# RadioNetwork.net
KiCad netlist of a schematic drawn in EAGLE
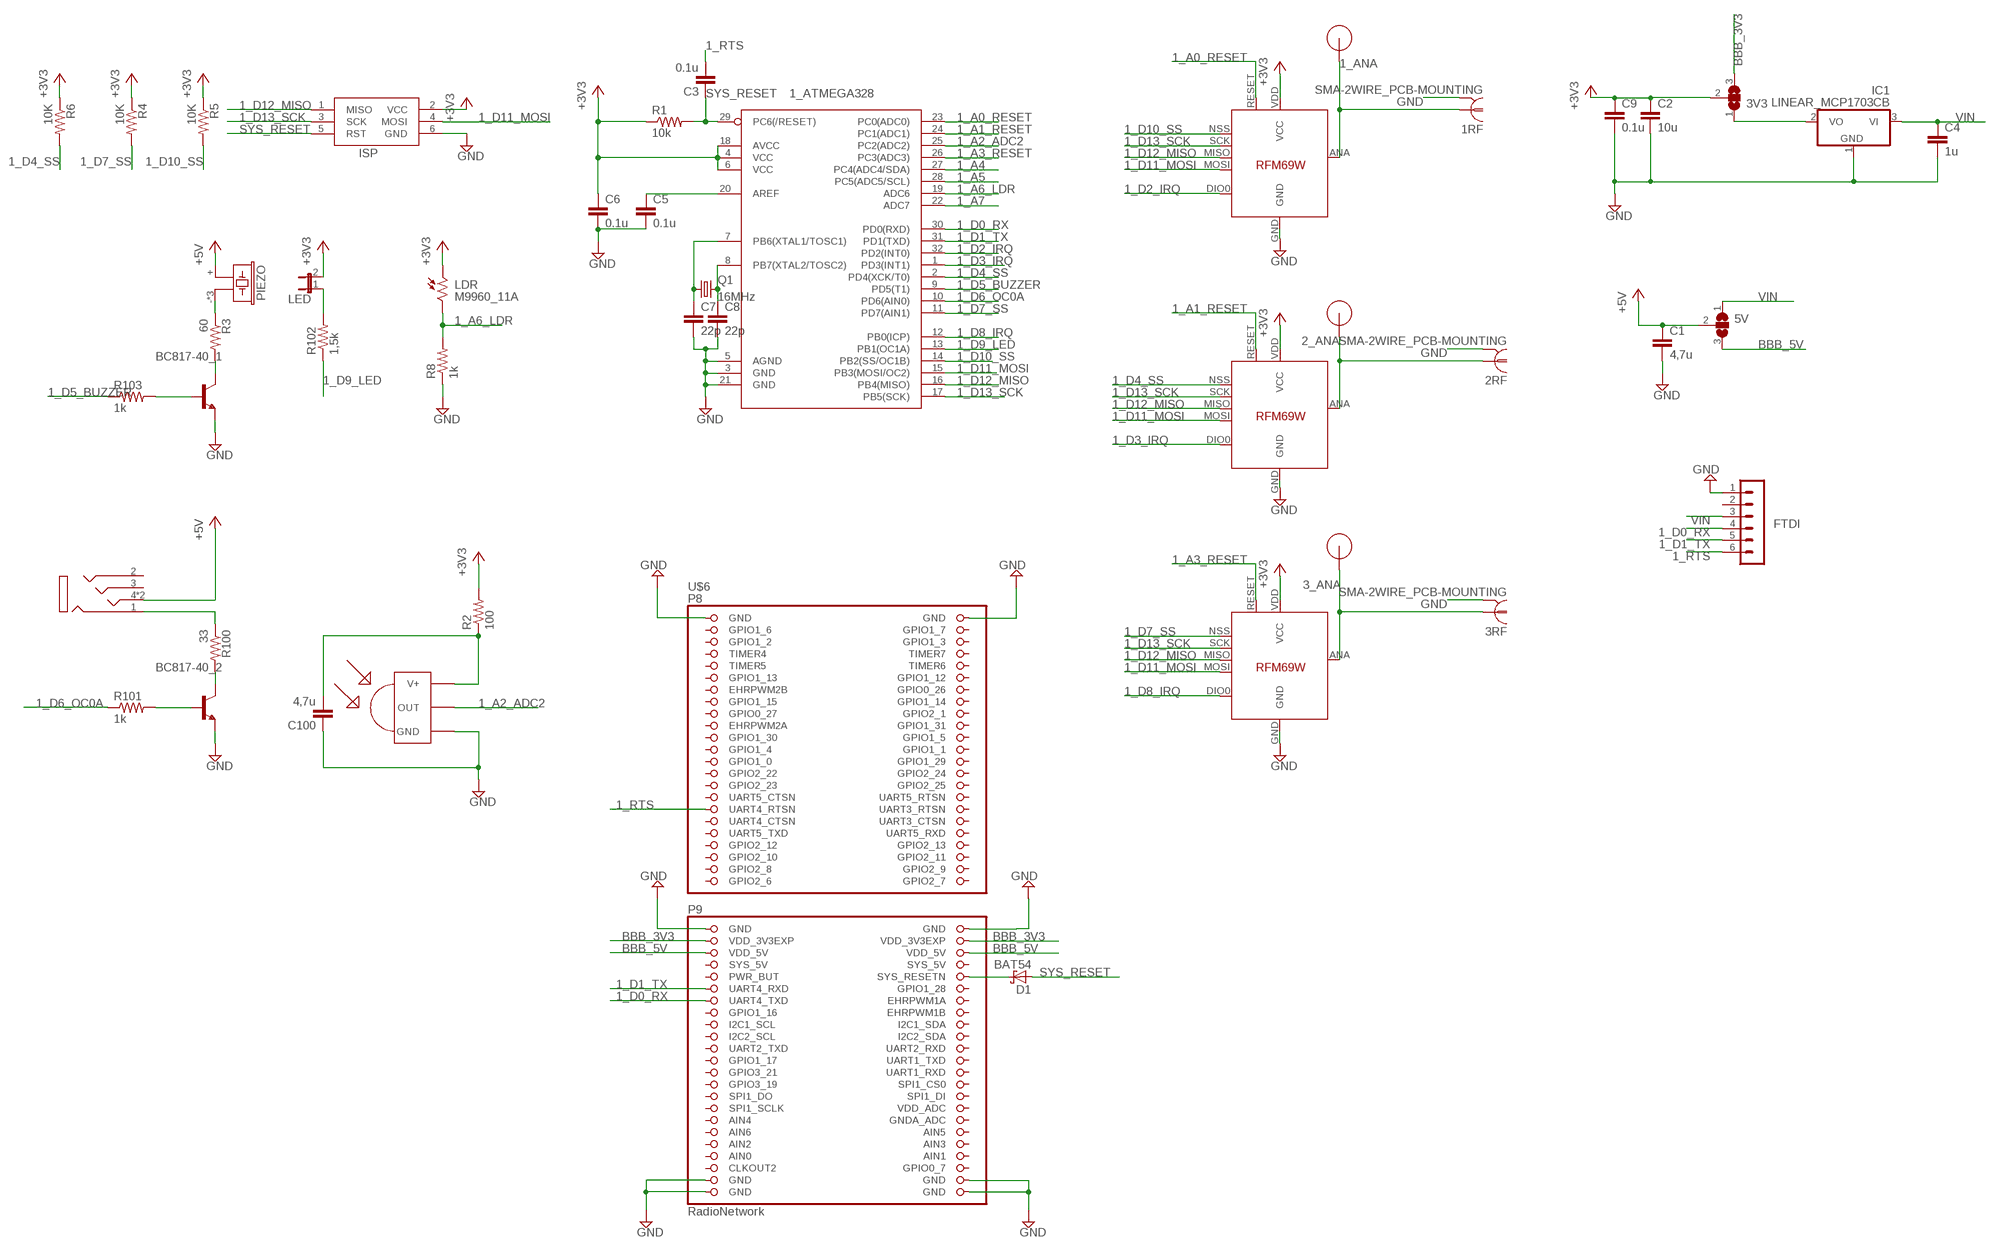
[diagram p0: schematic, sheet 1]

(export (version "E")
  (design (tool "Eeschema 10.0.6"))
  (components
    (comp (ref "1RF")
      (value "SMA-2WIRE_PCB-MOUNTING")
      (footprint "eagle-import:J01151A0931")
      (libsource (lib "eagle-import") (part "SMA-2WIRE_PCB-MOUNTING"))
    )
    (comp (ref "1_ATMEGA328")
      (value "ATMega-328")
      (footprint "eagle-import:TQFP32-08")
      (libsource (lib "eagle-import") (part "ATMEGA168/328TQFP32"))
    )
    (comp (ref "1_RFM69")
      (value "RFM69_MINIPADS")
      (footprint "eagle-import:RFM69W-MINPADS")
      (libsource (lib "eagle-import") (part "RFM69_MINIPADS"))
    )
    (comp (ref "2RF")
      (value "SMA-2WIRE_PCB-MOUNTING")
      (footprint "eagle-import:J01151A0931")
      (libsource (lib "eagle-import") (part "SMA-2WIRE_PCB-MOUNTING"))
    )
    (comp (ref "2_RFM69")
      (value "RFM69_MINIPADS")
      (footprint "eagle-import:RFM69W-MINPADS")
      (libsource (lib "eagle-import") (part "RFM69_MINIPADS"))
    )
    (comp (ref "3RF")
      (value "SMA-2WIRE_PCB-MOUNTING")
      (footprint "eagle-import:J01151A0931")
      (libsource (lib "eagle-import") (part "SMA-2WIRE_PCB-MOUNTING"))
    )
    (comp (ref "3V3")
      (value "SJ2W")
      (footprint "eagle-import:SJ_2")
      (libsource (lib "eagle-import") (part "SJ2W"))
    )
    (comp (ref "3_RFM69")
      (value "RFM69_MINIPADS")
      (footprint "eagle-import:RFM69W-MINPADS")
      (libsource (lib "eagle-import") (part "RFM69_MINIPADS"))
    )
    (comp (ref "5V")
      (value "SJ2W")
      (footprint "eagle-import:SJ_2")
      (libsource (lib "eagle-import") (part "SJ2W"))
    )
    (comp (ref "BC817-40_1")
      (value "BC817-40-NPN-SOT23-BEC")
      (footprint "eagle-import:SOT23-BEC")
      (libsource (lib "eagle-import") (part "-NPN-SOT23-BECBC817-40"))
    )
    (comp (ref "BC817-40_2")
      (value "BC817-40-NPN-SOT23-BEC")
      (footprint "eagle-import:SOT23-BEC")
      (libsource (lib "eagle-import") (part "-NPN-SOT23-BECBC817-40"))
    )
    (comp (ref "C1")
      (value "4,7u")
      (footprint "eagle-import:0603-CAP")
      (libsource (lib "eagle-import") (part "CAP0603-CAP"))
    )
    (comp (ref "C2")
      (value "10u")
      (footprint "eagle-import:0603-CAP")
      (libsource (lib "eagle-import") (part "CAP0603-CAP"))
    )
    (comp (ref "C3")
      (value "0.1u")
      (footprint "eagle-import:0603-CAP")
      (libsource (lib "eagle-import") (part "CAP0603-CAP"))
    )
    (comp (ref "C4")
      (value "1u")
      (footprint "eagle-import:0603-CAP")
      (libsource (lib "eagle-import") (part "CAP0603-CAP"))
    )
    (comp (ref "C5")
      (value "0.1u")
      (footprint "eagle-import:0603-CAP")
      (libsource (lib "eagle-import") (part "CAP0603-CAP"))
    )
    (comp (ref "C6")
      (value "0.1u")
      (footprint "eagle-import:0603-CAP")
      (libsource (lib "eagle-import") (part "CAP0603-CAP"))
    )
    (comp (ref "C7")
      (value "22p")
      (footprint "eagle-import:0603-CAP")
      (libsource (lib "eagle-import") (part "CAP0603-CAP"))
    )
    (comp (ref "C8")
      (value "22p")
      (footprint "eagle-import:0603-CAP")
      (libsource (lib "eagle-import") (part "CAP0603-CAP"))
    )
    (comp (ref "C9")
      (value "0.1u")
      (footprint "eagle-import:0603-CAP")
      (libsource (lib "eagle-import") (part "CAP0603-CAP"))
    )
    (comp (ref "C100")
      (value "4,7u")
      (footprint "eagle-import:0603-CAP")
      (libsource (lib "eagle-import") (part "CAP0603-CAP"))
    )
    (comp (ref "D1")
      (value "BAT54")
      (footprint "eagle-import:SOT23")
      (libsource (lib "eagle-import") (part "BAT54"))
    )
    (comp (ref "FTDI")
      (value "FTDI")
      (footprint "eagle-import:MA06-1")
      (libsource (lib "eagle-import") (part "MA06-1"))
    )
    (comp (ref "IC1")
      (value "LINEAR_MCP1703CB")
      (footprint "eagle-import:LINEAR_SOT23")
      (libsource (lib "eagle-import") (part "LINEAR_MCP1703CB"))
    )
    (comp (ref "IR-RX")
      (value "TSOP4836")
      (footprint "eagle-import:TSOP18XX")
      (libsource (lib "eagle-import") (part "TSOP4836"))
    )
    (comp (ref "IR-TX")
      (value "1503_13")
      (footprint "eagle-import:1503-03")
      (libsource (lib "eagle-import") (part "1503_13"))
    )
    (comp (ref "ISP")
      (value "AVRISP-6")
      (footprint "eagle-import:AVRISP")
      (libsource (lib "eagle-import") (part "AVRISP-6"))
    )
    (comp (ref "LDR")
      (value "M9960_11A")
      (footprint "eagle-import:M9960")
      (libsource (lib "eagle-import") (part "M9960_11A"))
    )
    (comp (ref "LED")
      (value "JP1E")
      (footprint "eagle-import:JP1")
      (libsource (lib "eagle-import") (part "JP1E"))
    )
    (comp (ref "PIEZO")
      (value "BUZZER-PIEZO_SMD")
      (footprint "eagle-import:BUZZER-PIEZO_SMD")
      (libsource (lib "eagle-import") (part "BUZZER-PIEZO_SMD"))
    )
    (comp (ref "Q1")
      (value "16MHz")
      (footprint "eagle-import:HC49_S")
      (libsource (lib "eagle-import") (part "CRYSTALHC49S"))
    )
    (comp (ref "R1")
      (value "10k")
      (footprint "eagle-import:0603-RES")
      (libsource (lib "eagle-import") (part "RESISTOR0603-RES"))
    )
    (comp (ref "R2")
      (value "100")
      (footprint "eagle-import:0603-RES")
      (libsource (lib "eagle-import") (part "RESISTOR0603-RES"))
    )
    (comp (ref "R3")
      (value "60")
      (footprint "eagle-import:0603-RES")
      (libsource (lib "eagle-import") (part "RESISTOR0603-RES"))
    )
    (comp (ref "R4")
      (value "10K")
      (footprint "eagle-import:0603-RES")
      (libsource (lib "eagle-import") (part "RESISTOR0603-RES"))
    )
    (comp (ref "R5")
      (value "10K")
      (footprint "eagle-import:0603-RES")
      (libsource (lib "eagle-import") (part "RESISTOR0603-RES"))
    )
    (comp (ref "R6")
      (value "10K")
      (footprint "eagle-import:0603-RES")
      (libsource (lib "eagle-import") (part "RESISTOR0603-RES"))
    )
    (comp (ref "R8")
      (value "1k")
      (footprint "eagle-import:0603-RES")
      (libsource (lib "eagle-import") (part "RESISTOR0603-RES"))
    )
    (comp (ref "R100")
      (value "33")
      (footprint "eagle-import:0603-RES")
      (libsource (lib "eagle-import") (part "RESISTOR0603-RES"))
    )
    (comp (ref "R101")
      (value "1k")
      (footprint "eagle-import:0603-RES")
      (libsource (lib "eagle-import") (part "RESISTOR0603-RES"))
    )
    (comp (ref "R102")
      (value "1,5k")
      (footprint "eagle-import:0603-RES")
      (libsource (lib "eagle-import") (part "RESISTOR0603-RES"))
    )
    (comp (ref "R103")
      (value "1k")
      (footprint "eagle-import:0603-RES")
      (libsource (lib "eagle-import") (part "RESISTOR0603-RES"))
    )
    (comp (ref "U$1")
      (value "RFM12B_ANTENNA")
      (footprint "eagle-import:RFM12B-ANTENNA")
      (libsource (lib "eagle-import") (part "RFM12B_ANTENNA"))
    )
    (comp (ref "U$2")
      (value "RFM12B_ANTENNA")
      (footprint "eagle-import:RFM12B-ANTENNA")
      (libsource (lib "eagle-import") (part "RFM12B_ANTENNA"))
    )
    (comp (ref "U$5")
      (value "RFM12B_ANTENNA")
      (footprint "eagle-import:RFM12B-ANTENNA")
      (libsource (lib "eagle-import") (part "RFM12B_ANTENNA"))
    )
    (comp (ref "U$6")
      (value "RadioNetwork")
      (footprint "eagle-import:BEAGLEBONE_SHIELD")
      (libsource (lib "eagle-import") (part "BEAGLEBONE_OUTLINE"))
    )
  )
  (nets
    (net (code "1") (name "+3V3") (class "Default")
      (node (ref "1_ATMEGA328") (pin "18") (pinfunction "AVCC_18") (pintype "bidirectional"))
      (node (ref "1_ATMEGA328") (pin "4") (pinfunction "VCC_4") (pintype "bidirectional"))
      (node (ref "1_ATMEGA328") (pin "6") (pinfunction "VCC_6") (pintype "bidirectional"))
      (node (ref "1_RFM69") (pin "VDD") (pinfunction "VCC_VDD") (pintype "power_in"))
      (node (ref "2_RFM69") (pin "VDD") (pinfunction "VCC_VDD") (pintype "power_in"))
      (node (ref "3V3") (pin "2") (pinfunction "2_2") (pintype "passive"))
      (node (ref "3_RFM69") (pin "VDD") (pinfunction "VCC_VDD") (pintype "power_in"))
      (node (ref "C2") (pin "1") (pinfunction "1_1") (pintype "passive"))
      (node (ref "C6") (pin "1") (pinfunction "1_1") (pintype "passive"))
      (node (ref "C9") (pin "1") (pinfunction "1_1") (pintype "passive"))
      (node (ref "ISP") (pin "2") (pinfunction "VCC_2") (pintype "power_in"))
      (node (ref "LDR") (pin "1") (pinfunction "1_1") (pintype "passive"))
      (node (ref "LED") (pin "2") (pinfunction "2_2") (pintype "passive"))
      (node (ref "R1") (pin "1") (pinfunction "1_1") (pintype "passive"))
      (node (ref "R2") (pin "2") (pinfunction "2_2") (pintype "passive"))
      (node (ref "R4") (pin "1") (pinfunction "1_1") (pintype "passive"))
      (node (ref "R5") (pin "1") (pinfunction "1_1") (pintype "passive"))
      (node (ref "R6") (pin "1") (pinfunction "1_1") (pintype "passive"))
    )
    (net (code "2") (name "+5V") (class "Default")
      (node (ref "5V") (pin "2") (pinfunction "2_2") (pintype "passive"))
      (node (ref "C1") (pin "1") (pinfunction "1_1") (pintype "passive"))
      (node (ref "IR-TX") (pin "4") (pinfunction "4_4") (pintype "bidirectional"))
      (node (ref "IR-TX") (pin "4-2") (pinfunction "4_4-2") (pintype "bidirectional"))
      (node (ref "PIEZO") (pin "+") (pinfunction "1_+") (pintype "passive"))
    )
    (net (code "3") (name "/1_A0_RESET") (class "Default")
      (node (ref "1_ATMEGA328") (pin "23") (pinfunction "PC0(ADC0)_23") (pintype "bidirectional"))
      (node (ref "1_RFM69") (pin "RESET") (pinfunction "RESET_RESET") (pintype "input"))
    )
    (net (code "4") (name "/1_A1_RESET") (class "Default")
      (node (ref "1_ATMEGA328") (pin "24") (pinfunction "PC1(ADC1)_24") (pintype "bidirectional"))
      (node (ref "2_RFM69") (pin "RESET") (pinfunction "RESET_RESET") (pintype "input"))
    )
    (net (code "5") (name "/1_A2_ADC2") (class "Default")
      (node (ref "1_ATMEGA328") (pin "25") (pinfunction "PC2(ADC2)_25") (pintype "bidirectional"))
      (node (ref "IR-RX") (pin "OUT") (pinfunction "OUT_OUT") (pintype "bidirectional"))
    )
    (net (code "6") (name "/1_A3_RESET") (class "Default")
      (node (ref "1_ATMEGA328") (pin "26") (pinfunction "PC3(ADC3)_26") (pintype "bidirectional"))
      (node (ref "3_RFM69") (pin "RESET") (pinfunction "RESET_RESET") (pintype "input"))
    )
    (net (code "7") (name "/1_A4") (class "Default")
      (node (ref "1_ATMEGA328") (pin "27") (pinfunction "PC4(ADC4/SDA)_27") (pintype "bidirectional"))
    )
    (net (code "8") (name "/1_A5") (class "Default")
      (node (ref "1_ATMEGA328") (pin "28") (pinfunction "PC5(ADC5/SCL)_28") (pintype "bidirectional"))
    )
    (net (code "9") (name "/1_A6_LDR") (class "Default")
      (node (ref "1_ATMEGA328") (pin "19") (pinfunction "ADC6_19") (pintype "bidirectional"))
      (node (ref "LDR") (pin "2") (pinfunction "2_2") (pintype "passive"))
      (node (ref "R8") (pin "2") (pinfunction "2_2") (pintype "passive"))
    )
    (net (code "10") (name "/1_A7") (class "Default")
      (node (ref "1_ATMEGA328") (pin "22") (pinfunction "ADC7_22") (pintype "bidirectional"))
    )
    (net (code "11") (name "/1_ANA") (class "Default")
      (node (ref "1RF") (pin "1") (pinfunction "1_1") (pintype "passive"))
      (node (ref "1_RFM69") (pin "ANA") (pinfunction "ANT_ANA") (pintype "passive"))
      (node (ref "U$1") (pin "P$1") (pinfunction "1_P$1") (pintype "bidirectional"))
    )
    (net (code "12") (name "/1_D0_RX") (class "Default")
      (node (ref "1_ATMEGA328") (pin "30") (pinfunction "PD0(RXD)_30") (pintype "bidirectional"))
      (node (ref "FTDI") (pin "4") (pinfunction "4_4") (pintype "passive"))
      (node (ref "U$6") (pin "59") (pinfunction "UART4_TXD_59") (pintype "passive"))
    )
    (net (code "13") (name "/1_D1_TX") (class "Default")
      (node (ref "1_ATMEGA328") (pin "31") (pinfunction "PD1(TXD)_31") (pintype "bidirectional"))
      (node (ref "FTDI") (pin "5") (pinfunction "5_5") (pintype "passive"))
      (node (ref "U$6") (pin "57") (pinfunction "UART4_RXD_57") (pintype "passive"))
    )
    (net (code "14") (name "/1_D2_IRQ") (class "Default")
      (node (ref "1_ATMEGA328") (pin "32") (pinfunction "PD2(INT0)_32") (pintype "bidirectional"))
      (node (ref "1_RFM69") (pin "DIO0") (pinfunction "DIO0/IRQ_DIO0") (pintype "open_collector"))
    )
    (net (code "15") (name "/1_D3_IRQ") (class "Default")
      (node (ref "1_ATMEGA328") (pin "1") (pinfunction "PD3(INT1)_1") (pintype "bidirectional"))
      (node (ref "2_RFM69") (pin "DIO0") (pinfunction "DIO0/IRQ_DIO0") (pintype "open_collector"))
    )
    (net (code "16") (name "/1_D4_SS") (class "Default")
      (node (ref "1_ATMEGA328") (pin "2") (pinfunction "PD4(XCK/T0)_2") (pintype "bidirectional"))
      (node (ref "2_RFM69") (pin "NSS") (pinfunction "SEL_NSS") (pintype "input"))
      (node (ref "R6") (pin "2") (pinfunction "2_2") (pintype "passive"))
    )
    (net (code "17") (name "/1_D5_BUZZER") (class "Default")
      (node (ref "1_ATMEGA328") (pin "9") (pinfunction "PD5(T1)_9") (pintype "bidirectional"))
      (node (ref "R103") (pin "1") (pinfunction "1_1") (pintype "passive"))
    )
    (net (code "18") (name "/1_D6_OC0A") (class "Default")
      (node (ref "1_ATMEGA328") (pin "10") (pinfunction "PD6(AIN0)_10") (pintype "bidirectional"))
      (node (ref "R101") (pin "1") (pinfunction "1_1") (pintype "passive"))
    )
    (net (code "19") (name "/1_D7_SS") (class "Default")
      (node (ref "1_ATMEGA328") (pin "11") (pinfunction "PD7(AIN1)_11") (pintype "bidirectional"))
      (node (ref "3_RFM69") (pin "NSS") (pinfunction "SEL_NSS") (pintype "input"))
      (node (ref "R4") (pin "2") (pinfunction "2_2") (pintype "passive"))
    )
    (net (code "20") (name "/1_D8_IRQ") (class "Default")
      (node (ref "1_ATMEGA328") (pin "12") (pinfunction "PB0(ICP)_12") (pintype "bidirectional"))
      (node (ref "3_RFM69") (pin "DIO0") (pinfunction "DIO0/IRQ_DIO0") (pintype "open_collector"))
    )
    (net (code "21") (name "/1_D9_LED") (class "Default")
      (node (ref "1_ATMEGA328") (pin "13") (pinfunction "PB1(OC1A)_13") (pintype "bidirectional"))
      (node (ref "R102") (pin "1") (pinfunction "1_1") (pintype "passive"))
    )
    (net (code "22") (name "/1_D10_SS") (class "Default")
      (node (ref "1_ATMEGA328") (pin "14") (pinfunction "PB2(SS/OC1B)_14") (pintype "bidirectional"))
      (node (ref "1_RFM69") (pin "NSS") (pinfunction "SEL_NSS") (pintype "input"))
      (node (ref "R5") (pin "2") (pinfunction "2_2") (pintype "passive"))
    )
    (net (code "23") (name "/1_D11_MOSI") (class "Default")
      (node (ref "1_ATMEGA328") (pin "15") (pinfunction "PB3(MOSI/OC2)_15") (pintype "bidirectional"))
      (node (ref "1_RFM69") (pin "MOSI") (pinfunction "MOSI_MOSI") (pintype "output"))
      (node (ref "2_RFM69") (pin "MOSI") (pinfunction "MOSI_MOSI") (pintype "output"))
      (node (ref "3_RFM69") (pin "MOSI") (pinfunction "MOSI_MOSI") (pintype "output"))
      (node (ref "ISP") (pin "4") (pinfunction "MOSI_4") (pintype "output"))
    )
    (net (code "24") (name "/1_D12_MISO") (class "Default")
      (node (ref "1_ATMEGA328") (pin "16") (pinfunction "PB4(MISO)_16") (pintype "bidirectional"))
      (node (ref "1_RFM69") (pin "MISO") (pinfunction "MISO_MISO") (pintype "input"))
      (node (ref "2_RFM69") (pin "MISO") (pinfunction "MISO_MISO") (pintype "input"))
      (node (ref "3_RFM69") (pin "MISO") (pinfunction "MISO_MISO") (pintype "input"))
      (node (ref "ISP") (pin "1") (pinfunction "MISO_1") (pintype "input"))
    )
    (net (code "25") (name "/1_D13_SCK") (class "Default")
      (node (ref "1_ATMEGA328") (pin "17") (pinfunction "PB5(SCK)_17") (pintype "bidirectional"))
      (node (ref "1_RFM69") (pin "SCK") (pinfunction "SCK_SCK") (pintype "input"))
      (node (ref "2_RFM69") (pin "SCK") (pinfunction "SCK_SCK") (pintype "input"))
      (node (ref "3_RFM69") (pin "SCK") (pinfunction "SCK_SCK") (pintype "input"))
      (node (ref "ISP") (pin "3") (pinfunction "SCK_3") (pintype "output"))
    )
    (net (code "26") (name "/1_RTS") (class "Default")
      (node (ref "C3") (pin "2") (pinfunction "2_2") (pintype "passive"))
      (node (ref "FTDI") (pin "6") (pinfunction "6_6") (pintype "passive"))
      (node (ref "U$6") (pin "33") (pinfunction "UART4_RTSN_33") (pintype "passive"))
    )
    (net (code "27") (name "/2_ANA") (class "Default")
      (node (ref "2RF") (pin "1") (pinfunction "1_1") (pintype "passive"))
      (node (ref "2_RFM69") (pin "ANA") (pinfunction "ANT_ANA") (pintype "passive"))
      (node (ref "U$5") (pin "P$1") (pinfunction "1_P$1") (pintype "bidirectional"))
    )
    (net (code "28") (name "/3_ANA") (class "Default")
      (node (ref "3RF") (pin "1") (pinfunction "1_1") (pintype "passive"))
      (node (ref "3_RFM69") (pin "ANA") (pinfunction "ANT_ANA") (pintype "passive"))
      (node (ref "U$2") (pin "P$1") (pinfunction "1_P$1") (pintype "bidirectional"))
    )
    (net (code "29") (name "/AIN0") (class "Default")
      (node (ref "U$6") (pin "85") (pinfunction "AIN0_85") (pintype "power_in"))
    )
    (net (code "30") (name "/BBB_3V3") (class "Default")
      (node (ref "3V3") (pin "3") (pinfunction "3_3") (pintype "passive"))
      (node (ref "U$6") (pin "49") (pinfunction "VDD_3V3EXP_49") (pintype "power_in"))
      (node (ref "U$6") (pin "50") (pinfunction "VDD_3V3EXP_50") (pintype "power_in"))
    )
    (net (code "31") (name "/BBB_5V") (class "Default")
      (node (ref "5V") (pin "3") (pinfunction "3_3") (pintype "passive"))
      (node (ref "U$6") (pin "51") (pinfunction "VDD_5V_51") (pintype "power_in"))
      (node (ref "U$6") (pin "52") (pinfunction "VDD_5V_52") (pintype "power_in"))
    )
    (net (code "32") (name "/SYS_5V") (class "Default")
      (node (ref "U$6") (pin "53") (pinfunction "SYS_5V_53") (pintype "power_in"))
    )
    (net (code "33") (name "/SYS_RESET") (class "Default")
      (node (ref "1_ATMEGA328") (pin "29") (pinfunction "PC6(/RESET)_29") (pintype "bidirectional"))
      (node (ref "C3") (pin "1") (pinfunction "1_1") (pintype "passive"))
      (node (ref "D1") (pin "1") (pinfunction "A_1") (pintype "passive"))
      (node (ref "ISP") (pin "5") (pinfunction "RST_5") (pintype "output"))
      (node (ref "R1") (pin "2") (pinfunction "2_2") (pintype "passive"))
    )
    (net (code "34") (name "/VIN") (class "Default")
      (node (ref "5V") (pin "1") (pinfunction "1_1") (pintype "passive"))
      (node (ref "C4") (pin "1") (pinfunction "1_1") (pintype "passive"))
      (node (ref "FTDI") (pin "3") (pinfunction "3_3") (pintype "passive"))
      (node (ref "IC1") (pin "3") (pinfunction "VI_3") (pintype "input"))
    )
    (net (code "35") (name "GND") (class "Default")
      (node (ref "1RF") (pin "G@1") (pinfunction "2_G@1") (pintype "passive"))
      (node (ref "1RF") (pin "G@2") (pinfunction "2_G@2") (pintype "passive"))
      (node (ref "1RF") (pin "G@3") (pinfunction "2_G@3") (pintype "passive"))
      (node (ref "1RF") (pin "G@4") (pinfunction "2_G@4") (pintype "passive"))
      (node (ref "1_ATMEGA328") (pin "21") (pinfunction "GND_21") (pintype "bidirectional"))
      (node (ref "1_ATMEGA328") (pin "3") (pinfunction "GND_3") (pintype "bidirectional"))
      (node (ref "1_ATMEGA328") (pin "5") (pinfunction "AGND_5") (pintype "bidirectional"))
      (node (ref "1_RFM69") (pin "GND") (pinfunction "GND_GND") (pintype "power_in"))
      (node (ref "2RF") (pin "G@1") (pinfunction "2_G@1") (pintype "passive"))
      (node (ref "2RF") (pin "G@2") (pinfunction "2_G@2") (pintype "passive"))
      (node (ref "2RF") (pin "G@3") (pinfunction "2_G@3") (pintype "passive"))
      (node (ref "2RF") (pin "G@4") (pinfunction "2_G@4") (pintype "passive"))
      (node (ref "2_RFM69") (pin "GND") (pinfunction "GND_GND") (pintype "power_in"))
      (node (ref "3RF") (pin "G@1") (pinfunction "2_G@1") (pintype "passive"))
      (node (ref "3RF") (pin "G@2") (pinfunction "2_G@2") (pintype "passive"))
      (node (ref "3RF") (pin "G@3") (pinfunction "2_G@3") (pintype "passive"))
      (node (ref "3RF") (pin "G@4") (pinfunction "2_G@4") (pintype "passive"))
      (node (ref "3_RFM69") (pin "GND") (pinfunction "GND_GND") (pintype "power_in"))
      (node (ref "BC817-40_1") (pin "E") (pinfunction "E_E") (pintype "passive"))
      (node (ref "BC817-40_2") (pin "E") (pinfunction "E_E") (pintype "passive"))
      (node (ref "C1") (pin "2") (pinfunction "2_2") (pintype "passive"))
      (node (ref "C100") (pin "1") (pinfunction "1_1") (pintype "passive"))
      (node (ref "C2") (pin "2") (pinfunction "2_2") (pintype "passive"))
      (node (ref "C4") (pin "2") (pinfunction "2_2") (pintype "passive"))
      (node (ref "C5") (pin "2") (pinfunction "2_2") (pintype "passive"))
      (node (ref "C6") (pin "2") (pinfunction "2_2") (pintype "passive"))
      (node (ref "C7") (pin "2") (pinfunction "2_2") (pintype "passive"))
      (node (ref "C8") (pin "2") (pinfunction "2_2") (pintype "passive"))
      (node (ref "C9") (pin "2") (pinfunction "2_2") (pintype "passive"))
      (node (ref "FTDI") (pin "1") (pinfunction "1_1") (pintype "passive"))
      (node (ref "IC1") (pin "1") (pinfunction "GND_1") (pintype "passive"))
      (node (ref "IR-RX") (pin "GND") (pinfunction "GND_GND") (pintype "bidirectional"))
      (node (ref "ISP") (pin "6") (pinfunction "GND_6") (pintype "power_in"))
      (node (ref "R8") (pin "1") (pinfunction "1_1") (pintype "passive"))
      (node (ref "U$6") (pin "1") (pinfunction "GND_1") (pintype "power_in"))
      (node (ref "U$6") (pin "2") (pinfunction "GND_2") (pintype "power_in"))
      (node (ref "U$6") (pin "47") (pinfunction "GND_47") (pintype "power_in"))
      (node (ref "U$6") (pin "48") (pinfunction "GND_48") (pintype "power_in"))
      (node (ref "U$6") (pin "89") (pinfunction "GND_89") (pintype "power_in"))
      (node (ref "U$6") (pin "90") (pinfunction "GND_90") (pintype "power_in"))
      (node (ref "U$6") (pin "91") (pinfunction "GND_91") (pintype "power_in"))
      (node (ref "U$6") (pin "92") (pinfunction "GND_92") (pintype "power_in"))
    )
    (net (code "36") (name "Net-(1_ATMEGA328-AREF)") (class "Default")
      (node (ref "1_ATMEGA328") (pin "20") (pinfunction "AREF_20") (pintype "bidirectional"))
      (node (ref "C5") (pin "1") (pinfunction "1_1") (pintype "passive"))
    )
    (net (code "37") (name "Net-(1_ATMEGA328-PB6(XTAL1{slash}TOSC1))") (class "Default")
      (node (ref "1_ATMEGA328") (pin "7") (pinfunction "PB6(XTAL1/TOSC1)_7") (pintype "bidirectional"))
      (node (ref "C7") (pin "1") (pinfunction "1_1") (pintype "passive"))
      (node (ref "Q1") (pin "1") (pinfunction "1_1") (pintype "passive"))
    )
    (net (code "38") (name "Net-(1_ATMEGA328-PB7(XTAL2{slash}TOSC2))") (class "Default")
      (node (ref "1_ATMEGA328") (pin "8") (pinfunction "PB7(XTAL2/TOSC2)_8") (pintype "bidirectional"))
      (node (ref "C8") (pin "1") (pinfunction "1_1") (pintype "passive"))
      (node (ref "Q1") (pin "2") (pinfunction "2_2") (pintype "passive"))
    )
    (net (code "39") (name "Net-(BC817-40_1-PadB)") (class "Default")
      (node (ref "BC817-40_1") (pin "B") (pinfunction "B_B") (pintype "passive"))
      (node (ref "R103") (pin "2") (pinfunction "2_2") (pintype "passive"))
    )
    (net (code "40") (name "Net-(BC817-40_1-PadC)") (class "Default")
      (node (ref "BC817-40_1") (pin "C") (pinfunction "C_C") (pintype "passive"))
      (node (ref "R3") (pin "2") (pinfunction "2_2") (pintype "passive"))
    )
    (net (code "41") (name "Net-(BC817-40_2-PadB)") (class "Default")
      (node (ref "BC817-40_2") (pin "B") (pinfunction "B_B") (pintype "passive"))
      (node (ref "R101") (pin "2") (pinfunction "2_2") (pintype "passive"))
    )
    (net (code "42") (name "Net-(BC817-40_2-PadC)") (class "Default")
      (node (ref "BC817-40_2") (pin "C") (pinfunction "C_C") (pintype "passive"))
      (node (ref "R100") (pin "2") (pinfunction "2_2") (pintype "passive"))
    )
    (net (code "43") (name "Net-(D1-C)") (class "Default")
      (node (ref "D1") (pin "3") (pinfunction "C_3") (pintype "passive"))
      (node (ref "U$6") (pin "56") (pinfunction "SYS_RESETN_56") (pintype "passive"))
    )
    (net (code "44") (name "Net-(IC1-VO)") (class "Default")
      (node (ref "3V3") (pin "1") (pinfunction "1_1") (pintype "passive"))
      (node (ref "IC1") (pin "2") (pinfunction "VO_2") (pintype "passive"))
    )
    (net (code "45") (name "Net-(IR-RX-V+)") (class "Default")
      (node (ref "C100") (pin "2") (pinfunction "2_2") (pintype "passive"))
      (node (ref "IR-RX") (pin "VCC") (pinfunction "V+_VCC") (pintype "bidirectional"))
      (node (ref "R2") (pin "1") (pinfunction "1_1") (pintype "passive"))
    )
    (net (code "46") (name "Net-(IR-TX-Pad1)") (class "Default")
      (node (ref "IR-TX") (pin "1") (pinfunction "1_1") (pintype "bidirectional"))
      (node (ref "R100") (pin "1") (pinfunction "1_1") (pintype "passive"))
    )
    (net (code "47") (name "Net-(LED-Pad1)") (class "Default")
      (node (ref "LED") (pin "1") (pinfunction "1_1") (pintype "passive"))
      (node (ref "R102") (pin "2") (pinfunction "2_2") (pintype "passive"))
    )
    (net (code "48") (name "Net-(PIEZO-2-Pad-)") (class "Default")
      (node (ref "PIEZO") (pin "-") (pinfunction "2_-") (pintype "passive"))
      (node (ref "PIEZO") (pin "DUMMY") (pinfunction "2_DUMMY") (pintype "passive"))
      (node (ref "PIEZO") (pin "DUMMY1") (pinfunction "2_DUMMY1") (pintype "passive"))
      (node (ref "R3") (pin "1") (pinfunction "1_1") (pintype "passive"))
    )
    (net (code "49") (name "unconnected-(FTDI-Pad2)") (class "Default")
      (node (ref "FTDI") (pin "2") (pinfunction "2_2") (pintype "passive"))
    )
    (net (code "50") (name "unconnected-(IR-TX-Pad2)") (class "Default")
      (node (ref "IR-TX") (pin "2") (pinfunction "2_2") (pintype "bidirectional"))
    )
    (net (code "51") (name "unconnected-(IR-TX-Pad3)") (class "Default")
      (node (ref "IR-TX") (pin "3") (pinfunction "3_3") (pintype "bidirectional"))
    )
    (net (code "52") (name "unconnected-(U$6-AIN1-Pad86)") (class "Default")
      (node (ref "U$6") (pin "86") (pinfunction "AIN1_86") (pintype "passive"))
    )
    (net (code "53") (name "unconnected-(U$6-AIN2-Pad83)") (class "Default")
      (node (ref "U$6") (pin "83") (pinfunction "AIN2_83") (pintype "passive"))
    )
    (net (code "54") (name "unconnected-(U$6-AIN3-Pad84)") (class "Default")
      (node (ref "U$6") (pin "84") (pinfunction "AIN3_84") (pintype "passive"))
    )
    (net (code "55") (name "unconnected-(U$6-AIN4-Pad79)") (class "Default")
      (node (ref "U$6") (pin "79") (pinfunction "AIN4_79") (pintype "passive"))
    )
    (net (code "56") (name "unconnected-(U$6-AIN5-Pad82)") (class "Default")
      (node (ref "U$6") (pin "82") (pinfunction "AIN5_82") (pintype "passive"))
    )
    (net (code "57") (name "unconnected-(U$6-AIN6-Pad81)") (class "Default")
      (node (ref "U$6") (pin "81") (pinfunction "AIN6_81") (pintype "passive"))
    )
    (net (code "58") (name "unconnected-(U$6-CLKOUT2-Pad87)") (class "Default")
      (node (ref "U$6") (pin "87") (pinfunction "CLKOUT2_87") (pintype "input"))
    )
    (net (code "59") (name "unconnected-(U$6-EHRPWM1A-Pad60)") (class "Default")
      (node (ref "U$6") (pin "60") (pinfunction "EHRPWM1A_60") (pintype "passive"))
    )
    (net (code "60") (name "unconnected-(U$6-EHRPWM1B-Pad62)") (class "Default")
      (node (ref "U$6") (pin "62") (pinfunction "EHRPWM1B_62") (pintype "passive"))
    )
    (net (code "61") (name "unconnected-(U$6-EHRPWM2A-Pad19)") (class "Default")
      (node (ref "U$6") (pin "19") (pinfunction "EHRPWM2A_19") (pintype "passive"))
    )
    (net (code "62") (name "unconnected-(U$6-EHRPWM2B-Pad13)") (class "Default")
      (node (ref "U$6") (pin "13") (pinfunction "EHRPWM2B_13") (pintype "passive"))
    )
    (net (code "63") (name "unconnected-(U$6-GNDA_ADC-Pad80)") (class "Default")
      (node (ref "U$6") (pin "80") (pinfunction "GNDA_ADC_80") (pintype "passive"))
    )
    (net (code "64") (name "unconnected-(U$6-GPIO0_7-Pad88)") (class "Default")
      (node (ref "U$6") (pin "88") (pinfunction "GPIO0_7_88") (pintype "passive"))
    )
    (net (code "65") (name "unconnected-(U$6-GPIO0_26-Pad14)") (class "Default")
      (node (ref "U$6") (pin "14") (pinfunction "GPIO0_26_14") (pintype "passive"))
    )
    (net (code "66") (name "unconnected-(U$6-GPIO0_27-Pad17)") (class "Default")
      (node (ref "U$6") (pin "17") (pinfunction "GPIO0_27_17") (pintype "passive"))
    )
    (net (code "67") (name "unconnected-(U$6-GPIO1_0-Pad25)") (class "Default")
      (node (ref "U$6") (pin "25") (pinfunction "GPIO1_0_25") (pintype "passive"))
    )
    (net (code "68") (name "unconnected-(U$6-GPIO1_1-Pad24)") (class "Default")
      (node (ref "U$6") (pin "24") (pinfunction "GPIO1_1_24") (pintype "passive"))
    )
    (net (code "69") (name "unconnected-(U$6-GPIO1_2-Pad5)") (class "Default")
      (node (ref "U$6") (pin "5") (pinfunction "GPIO1_2_5") (pintype "passive"))
    )
    (net (code "70") (name "unconnected-(U$6-GPIO1_3-Pad6)") (class "Default")
      (node (ref "U$6") (pin "6") (pinfunction "GPIO1_3_6") (pintype "passive"))
    )
    (net (code "71") (name "unconnected-(U$6-GPIO1_4-Pad23)") (class "Default")
      (node (ref "U$6") (pin "23") (pinfunction "GPIO1_4_23") (pintype "passive"))
    )
    (net (code "72") (name "unconnected-(U$6-GPIO1_5-Pad22)") (class "Default")
      (node (ref "U$6") (pin "22") (pinfunction "GPIO1_5_22") (pintype "passive"))
    )
    (net (code "73") (name "unconnected-(U$6-GPIO1_6-Pad3)") (class "Default")
      (node (ref "U$6") (pin "3") (pinfunction "GPIO1_6_3") (pintype "passive"))
    )
    (net (code "74") (name "unconnected-(U$6-GPIO1_7-Pad4)") (class "Default")
      (node (ref "U$6") (pin "4") (pinfunction "GPIO1_7_4") (pintype "passive"))
    )
    (net (code "75") (name "unconnected-(U$6-GPIO1_12-Pad12)") (class "Default")
      (node (ref "U$6") (pin "12") (pinfunction "GPIO1_12_12") (pintype "passive"))
    )
    (net (code "76") (name "unconnected-(U$6-GPIO1_13-Pad11)") (class "Default")
      (node (ref "U$6") (pin "11") (pinfunction "GPIO1_13_11") (pintype "passive"))
    )
    (net (code "77") (name "unconnected-(U$6-GPIO1_14-Pad16)") (class "Default")
      (node (ref "U$6") (pin "16") (pinfunction "GPIO1_14_16") (pintype "passive"))
    )
    (net (code "78") (name "unconnected-(U$6-GPIO1_15-Pad15)") (class "Default")
      (node (ref "U$6") (pin "15") (pinfunction "GPIO1_15_15") (pintype "passive"))
    )
    (net (code "79") (name "unconnected-(U$6-GPIO1_16-Pad61)") (class "Default")
      (node (ref "U$6") (pin "61") (pinfunction "GPIO1_16_61") (pintype "passive"))
    )
    (net (code "80") (name "unconnected-(U$6-GPIO1_17-Pad69)") (class "Default")
      (node (ref "U$6") (pin "69") (pinfunction "GPIO1_17_69") (pintype "passive"))
    )
    (net (code "81") (name "unconnected-(U$6-GPIO1_28-Pad58)") (class "Default")
      (node (ref "U$6") (pin "58") (pinfunction "GPIO1_28_58") (pintype "passive"))
    )
    (net (code "82") (name "unconnected-(U$6-GPIO1_29-Pad26)") (class "Default")
      (node (ref "U$6") (pin "26") (pinfunction "GPIO1_29_26") (pintype "passive"))
    )
    (net (code "83") (name "unconnected-(U$6-GPIO1_30-Pad21)") (class "Default")
      (node (ref "U$6") (pin "21") (pinfunction "GPIO1_30_21") (pintype "passive"))
    )
    (net (code "84") (name "unconnected-(U$6-GPIO1_31-Pad20)") (class "Default")
      (node (ref "U$6") (pin "20") (pinfunction "GPIO1_31_20") (pintype "passive"))
    )
    (net (code "85") (name "unconnected-(U$6-GPIO2_1-Pad18)") (class "Default")
      (node (ref "U$6") (pin "18") (pinfunction "GPIO2_1_18") (pintype "passive"))
    )
    (net (code "86") (name "unconnected-(U$6-GPIO2_6-Pad45)") (class "Default")
      (node (ref "U$6") (pin "45") (pinfunction "GPIO2_6_45") (pintype "passive"))
    )
    (net (code "87") (name "unconnected-(U$6-GPIO2_7-Pad46)") (class "Default")
      (node (ref "U$6") (pin "46") (pinfunction "GPIO2_7_46") (pintype "passive"))
    )
    (net (code "88") (name "unconnected-(U$6-GPIO2_8-Pad43)") (class "Default")
      (node (ref "U$6") (pin "43") (pinfunction "GPIO2_8_43") (pintype "passive"))
    )
    (net (code "89") (name "unconnected-(U$6-GPIO2_9-Pad44)") (class "Default")
      (node (ref "U$6") (pin "44") (pinfunction "GPIO2_9_44") (pintype "passive"))
    )
    (net (code "90") (name "unconnected-(U$6-GPIO2_10-Pad41)") (class "Default")
      (node (ref "U$6") (pin "41") (pinfunction "GPIO2_10_41") (pintype "passive"))
    )
    (net (code "91") (name "unconnected-(U$6-GPIO2_11-Pad42)") (class "Default")
      (node (ref "U$6") (pin "42") (pinfunction "GPIO2_11_42") (pintype "passive"))
    )
    (net (code "92") (name "unconnected-(U$6-GPIO2_12-Pad39)") (class "Default")
      (node (ref "U$6") (pin "39") (pinfunction "GPIO2_12_39") (pintype "passive"))
    )
    (net (code "93") (name "unconnected-(U$6-GPIO2_13-Pad40)") (class "Default")
      (node (ref "U$6") (pin "40") (pinfunction "GPIO2_13_40") (pintype "passive"))
    )
    (net (code "94") (name "unconnected-(U$6-GPIO2_22-Pad27)") (class "Default")
      (node (ref "U$6") (pin "27") (pinfunction "GPIO2_22_27") (pintype "passive"))
    )
    (net (code "95") (name "unconnected-(U$6-GPIO2_23-Pad29)") (class "Default")
      (node (ref "U$6") (pin "29") (pinfunction "GPIO2_23_29") (pintype "passive"))
    )
    (net (code "96") (name "unconnected-(U$6-GPIO2_24-Pad28)") (class "Default")
      (node (ref "U$6") (pin "28") (pinfunction "GPIO2_24_28") (pintype "passive"))
    )
    (net (code "97") (name "unconnected-(U$6-GPIO2_25-Pad30)") (class "Default")
      (node (ref "U$6") (pin "30") (pinfunction "GPIO2_25_30") (pintype "passive"))
    )
    (net (code "98") (name "unconnected-(U$6-GPIO3_19-Pad73)") (class "Default")
      (node (ref "U$6") (pin "73") (pinfunction "GPIO3_19_73") (pintype "passive"))
    )
    (net (code "99") (name "unconnected-(U$6-GPIO3_21-Pad71)") (class "Default")
      (node (ref "U$6") (pin "71") (pinfunction "GPIO3_21_71") (pintype "passive"))
    )
    (net (code "100") (name "unconnected-(U$6-I2C1_SCL-Pad63)") (class "Default")
      (node (ref "U$6") (pin "63") (pinfunction "I2C1_SCL_63") (pintype "passive"))
    )
    (net (code "101") (name "unconnected-(U$6-I2C1_SDA-Pad64)") (class "Default")
      (node (ref "U$6") (pin "64") (pinfunction "I2C1_SDA_64") (pintype "passive"))
    )
    (net (code "102") (name "unconnected-(U$6-I2C2_SCL-Pad65)") (class "Default")
      (node (ref "U$6") (pin "65") (pinfunction "I2C2_SCL_65") (pintype "passive"))
    )
    (net (code "103") (name "unconnected-(U$6-I2C2_SDA-Pad66)") (class "Default")
      (node (ref "U$6") (pin "66") (pinfunction "I2C2_SDA_66") (pintype "passive"))
    )
    (net (code "104") (name "unconnected-(U$6-PWR_BUT-Pad55)") (class "Default")
      (node (ref "U$6") (pin "55") (pinfunction "PWR_BUT_55") (pintype "passive"))
    )
    (net (code "105") (name "unconnected-(U$6-SPI1_CS0-Pad74)") (class "Default")
      (node (ref "U$6") (pin "74") (pinfunction "SPI1_CS0_74") (pintype "passive"))
    )
    (net (code "106") (name "unconnected-(U$6-SPI1_DI-Pad76)") (class "Default")
      (node (ref "U$6") (pin "76") (pinfunction "SPI1_DI_76") (pintype "passive"))
    )
    (net (code "107") (name "unconnected-(U$6-SPI1_DO-Pad75)") (class "Default")
      (node (ref "U$6") (pin "75") (pinfunction "SPI1_DO_75") (pintype "passive"))
    )
    (net (code "108") (name "unconnected-(U$6-SPI1_SCLK-Pad77)") (class "Default")
      (node (ref "U$6") (pin "77") (pinfunction "SPI1_SCLK_77") (pintype "passive"))
    )
    (net (code "109") (name "unconnected-(U$6-SYS_5V-Pad54)") (class "Default")
      (node (ref "U$6") (pin "54") (pinfunction "SYS_5V_54") (pintype "passive"))
    )
    (net (code "110") (name "unconnected-(U$6-TIMER4-Pad7)") (class "Default")
      (node (ref "U$6") (pin "7") (pinfunction "TIMER4_7") (pintype "passive"))
    )
    (net (code "111") (name "unconnected-(U$6-TIMER5-Pad9)") (class "Default")
      (node (ref "U$6") (pin "9") (pinfunction "TIMER5_9") (pintype "passive"))
    )
    (net (code "112") (name "unconnected-(U$6-TIMER6-Pad10)") (class "Default")
      (node (ref "U$6") (pin "10") (pinfunction "TIMER6_10") (pintype "passive"))
    )
    (net (code "113") (name "unconnected-(U$6-TIMER7-Pad8)") (class "Default")
      (node (ref "U$6") (pin "8") (pinfunction "TIMER7_8") (pintype "passive"))
    )
    (net (code "114") (name "unconnected-(U$6-UART1_RXD-Pad72)") (class "Default")
      (node (ref "U$6") (pin "72") (pinfunction "UART1_RXD_72") (pintype "passive"))
    )
    (net (code "115") (name "unconnected-(U$6-UART1_TXD-Pad70)") (class "Default")
      (node (ref "U$6") (pin "70") (pinfunction "UART1_TXD_70") (pintype "passive"))
    )
    (net (code "116") (name "unconnected-(U$6-UART2_RXD-Pad68)") (class "Default")
      (node (ref "U$6") (pin "68") (pinfunction "UART2_RXD_68") (pintype "passive"))
    )
    (net (code "117") (name "unconnected-(U$6-UART2_TXD-Pad67)") (class "Default")
      (node (ref "U$6") (pin "67") (pinfunction "UART2_TXD_67") (pintype "passive"))
    )
    (net (code "118") (name "unconnected-(U$6-UART3_CTSN-Pad36)") (class "Default")
      (node (ref "U$6") (pin "36") (pinfunction "UART3_CTSN_36") (pintype "passive"))
    )
    (net (code "119") (name "unconnected-(U$6-UART3_RTSN-Pad34)") (class "Default")
      (node (ref "U$6") (pin "34") (pinfunction "UART3_RTSN_34") (pintype "passive"))
    )
    (net (code "120") (name "unconnected-(U$6-UART4_CTSN-Pad35)") (class "Default")
      (node (ref "U$6") (pin "35") (pinfunction "UART4_CTSN_35") (pintype "passive"))
    )
    (net (code "121") (name "unconnected-(U$6-UART5_CTSN-Pad31)") (class "Default")
      (node (ref "U$6") (pin "31") (pinfunction "UART5_CTSN_31") (pintype "passive"))
    )
    (net (code "122") (name "unconnected-(U$6-UART5_RTSN-Pad32)") (class "Default")
      (node (ref "U$6") (pin "32") (pinfunction "UART5_RTSN_32") (pintype "passive"))
    )
    (net (code "123") (name "unconnected-(U$6-UART5_RXD-Pad38)") (class "Default")
      (node (ref "U$6") (pin "38") (pinfunction "UART5_RXD_38") (pintype "passive"))
    )
    (net (code "124") (name "unconnected-(U$6-UART5_TXD-Pad37)") (class "Default")
      (node (ref "U$6") (pin "37") (pinfunction "UART5_TXD_37") (pintype "passive"))
    )
    (net (code "125") (name "unconnected-(U$6-VDD_ADC-Pad78)") (class "Default")
      (node (ref "U$6") (pin "78") (pinfunction "VDD_ADC_78") (pintype "passive"))
    )
  )
)
